# golgi_bot_H_bridge.net
KiCad netlist of a schematic drawn in Altium Designer
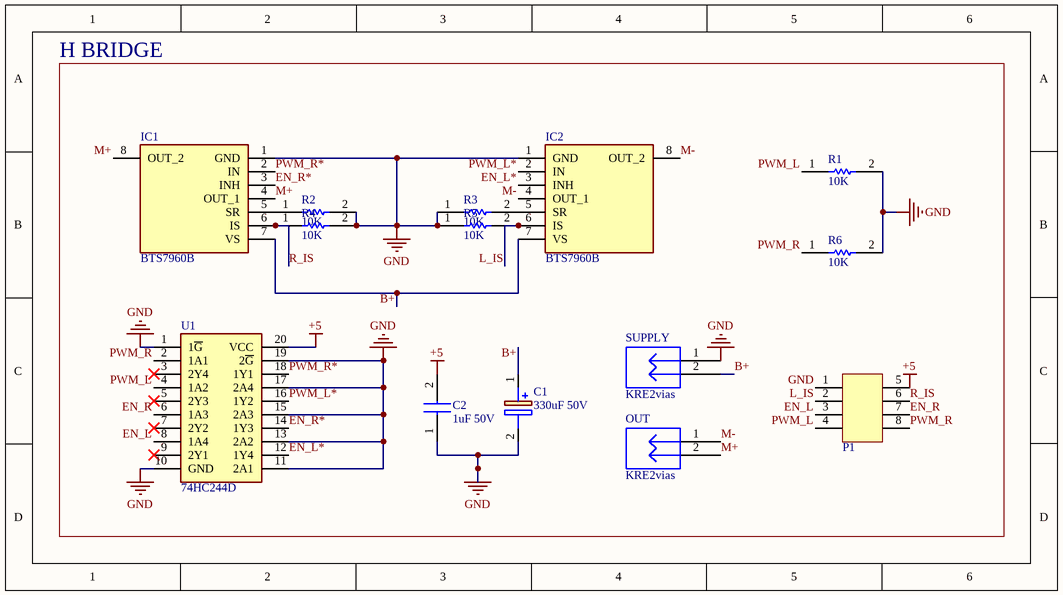
[diagram p0: golgi_bot_H_bridge.SchDoc]

(export (version "E")
  (design (tool "Eeschema 10.0.6"))
  (components
    (comp (ref "C1")
      (value "330uF 50V")
      (footprint "golgi_bot_H_bridge:CAPPRD750W85D1600H1650")
      (description "capacitor 330uf 50V")
      (fields (field (name "MANUFACTURER_PART_NUMBER") "EEU-TA1H331S"))
      (libsource (lib "golgi_bot_H_bridge") (part "Capacitor eletrolítico"))
    )
    (comp (ref "C2")
      (value "1uF 50V")
      (footprint "SamacSys:CAPC3216X180N")
      (description "Capacitor")
      (fields
        (field (name "MANUFACTURER_PART_NUMBER") "C3216X5R0J226M160AA")
        (field (name "MOUSER PART NUMBER") "810-C3216X5R0J226M-6")
      )
      (libsource (lib "golgi_bot_H_bridge") (part "Capacitor Cerâmico 1206"))
    )
    (comp (ref "IC1")
      (value "BTS7960B")
      (footprint "BTS7960B")
      (description "Integrated Circuit")
      (libsource (lib "") (part "BTS7960B_1"))
    )
    (comp (ref "IC2")
      (value "BTS7960B")
      (footprint "BTS7960B")
      (description "Integrated Circuit")
      (libsource (lib "golgi_bot_H_bridge") (part "BTS7960B"))
    )
    (comp (ref "OUT")
      (value "KRE2vias")
      (footprint "KRE2-2vias")
      (description "Conector 2 vias")
      (libsource (lib "golgi_bot_H_bridge") (part "KRE2vias"))
    )
    (comp (ref "P1")
      (value "PIN BAR 2X4")
      (footprint "MALE PIN BAR 2X4")
      (fields (field (name "MANUFACTURER") "Cromax"))
      (libsource (lib "golgi_bot_H_bridge") (part "Male pin bar 2x4"))
    )
    (comp (ref "R1")
      (value "10K")
      (footprint "RESC3216X60N")
      (fields
        (field (name "MANUFACTURER_PART_NUMBER") "CRCW12064K70FKEA")
        (field (name "MOUSER PART NUMBER") "71-CRCW1206-4.7K-E3")
      )
      (libsource (lib "golgi_bot_H_bridge") (part "Resistor 1206"))
    )
    (comp (ref "R2")
      (value "10K")
      (footprint "RESC3216X60N")
      (fields
        (field (name "MANUFACTURER_PART_NUMBER") "CRCW12064K70FKEA")
        (field (name "MOUSER PART NUMBER") "71-CRCW1206-4.7K-E3")
      )
      (libsource (lib "golgi_bot_H_bridge") (part "Resistor 1206"))
    )
    (comp (ref "R3")
      (value "10K")
      (footprint "RESC3216X60N")
      (fields
        (field (name "MANUFACTURER_PART_NUMBER") "CRCW12064K70FKEA")
        (field (name "MOUSER PART NUMBER") "71-CRCW1206-4.7K-E3")
      )
      (libsource (lib "golgi_bot_H_bridge") (part "Resistor 1206"))
    )
    (comp (ref "R4")
      (value "10K")
      (footprint "RESC3216X60N")
      (fields
        (field (name "MANUFACTURER_PART_NUMBER") "CRCW12064K70FKEA")
        (field (name "MOUSER PART NUMBER") "71-CRCW1206-4.7K-E3")
      )
      (libsource (lib "golgi_bot_H_bridge") (part "Resistor 1206"))
    )
    (comp (ref "R5")
      (value "10K")
      (footprint "RESC3216X60N")
      (fields
        (field (name "MANUFACTURER_PART_NUMBER") "CRCW12064K70FKEA")
        (field (name "MOUSER PART NUMBER") "71-CRCW1206-4.7K-E3")
      )
      (libsource (lib "golgi_bot_H_bridge") (part "Resistor 1206"))
    )
    (comp (ref "R6")
      (value "10K")
      (footprint "RESC3216X60N")
      (fields
        (field (name "MANUFACTURER_PART_NUMBER") "CRCW12064K70FKEA")
        (field (name "MOUSER PART NUMBER") "71-CRCW1206-4.7K-E3")
      )
      (libsource (lib "golgi_bot_H_bridge") (part "Resistor 1206"))
    )
    (comp (ref "SUPPLY")
      (value "KRE2vias")
      (footprint "KRE2-2vias")
      (description "Conector 2 vias")
      (libsource (lib "golgi_bot_H_bridge") (part "KRE2vias"))
    )
    (comp (ref "U1")
      (value "74HC244D")
      (footprint "SOIC127P1030X250-20N")
      (description "Integrated Circuit")
      (fields (field (name "MOUSER PART NUMBER") "757-74HC244D"))
      (libsource (lib "golgi_bot_H_bridge") (part "74HC244D"))
    )
  )
  (nets
    (net (code "1") (name "+5") (class "Default")
      (node (ref "C2") (pin "2") (pinfunction "2_2") (pintype "passive"))
      (node (ref "P1") (pin "5") (pintype "passive"))
      (node (ref "U1") (pin "20") (pinfunction "VCC_20") (pintype "passive"))
    )
    (net (code "2") (name "/B+") (class "Default")
      (node (ref "C1") (pin "1") (pinfunction "+_1") (pintype "passive"))
      (node (ref "IC1") (pin "7") (pinfunction "VS_7") (pintype "passive"))
      (node (ref "IC2") (pin "7") (pinfunction "VS_7") (pintype "passive"))
      (node (ref "SUPPLY") (pin "2") (pintype "passive"))
    )
    (net (code "3") (name "/EN_L") (class "Default")
      (node (ref "P1") (pin "3") (pintype "passive"))
      (node (ref "U1") (pin "8") (pinfunction "1A4_8") (pintype "passive"))
    )
    (net (code "4") (name "/EN_L*") (class "Default")
      (node (ref "IC2") (pin "3") (pinfunction "INH_3") (pintype "passive"))
      (node (ref "U1") (pin "12") (pinfunction "1Y4_12") (pintype "passive"))
    )
    (net (code "5") (name "/EN_R") (class "Default")
      (node (ref "P1") (pin "7") (pintype "passive"))
      (node (ref "U1") (pin "6") (pinfunction "1A3_6") (pintype "passive"))
    )
    (net (code "6") (name "/EN_R*") (class "Default")
      (node (ref "IC1") (pin "3") (pinfunction "INH_3") (pintype "passive"))
      (node (ref "U1") (pin "14") (pinfunction "1Y3_14") (pintype "passive"))
    )
    (net (code "7") (name "/L_IS") (class "Default")
      (node (ref "IC2") (pin "6") (pinfunction "IS_6") (pintype "passive"))
      (node (ref "P1") (pin "2") (pintype "passive"))
      (node (ref "R5") (pin "2") (pinfunction "2_2") (pintype "passive"))
    )
    (net (code "8") (name "/M+") (class "Default")
      (node (ref "IC1") (pin "4") (pinfunction "OUT_1_4") (pintype "passive"))
      (node (ref "IC1") (pin "8") (pinfunction "OUT_2_8") (pintype "passive"))
      (node (ref "OUT") (pin "2") (pintype "passive"))
    )
    (net (code "9") (name "/M-") (class "Default")
      (node (ref "IC2") (pin "4") (pinfunction "OUT_1_4") (pintype "passive"))
      (node (ref "IC2") (pin "8") (pinfunction "OUT_2_8") (pintype "passive"))
      (node (ref "OUT") (pin "1") (pintype "passive"))
    )
    (net (code "10") (name "/PWM_L") (class "Default")
      (node (ref "P1") (pin "4") (pintype "passive"))
      (node (ref "R1") (pin "1") (pinfunction "1_1") (pintype "passive"))
      (node (ref "U1") (pin "4") (pinfunction "1A2_4") (pintype "passive"))
    )
    (net (code "11") (name "/PWM_L*") (class "Default")
      (node (ref "IC2") (pin "2") (pinfunction "IN_2") (pintype "passive"))
      (node (ref "U1") (pin "16") (pinfunction "1Y2_16") (pintype "passive"))
    )
    (net (code "12") (name "/PWM_R") (class "Default")
      (node (ref "P1") (pin "8") (pintype "passive"))
      (node (ref "R6") (pin "1") (pinfunction "1_1") (pintype "passive"))
      (node (ref "U1") (pin "2") (pinfunction "1A1_2") (pintype "passive"))
    )
    (net (code "13") (name "/PWM_R*") (class "Default")
      (node (ref "IC1") (pin "2") (pinfunction "IN_2") (pintype "passive"))
      (node (ref "U1") (pin "18") (pinfunction "1Y1_18") (pintype "passive"))
    )
    (net (code "14") (name "/R_IS") (class "Default")
      (node (ref "IC1") (pin "6") (pinfunction "IS_6") (pintype "passive"))
      (node (ref "P1") (pin "6") (pintype "passive"))
      (node (ref "R4") (pin "1") (pinfunction "1_1") (pintype "passive"))
    )
    (net (code "15") (name "GND") (class "Default")
      (node (ref "C1") (pin "2") (pinfunction "-_2") (pintype "passive"))
      (node (ref "C2") (pin "1") (pinfunction "1_1") (pintype "passive"))
      (node (ref "IC1") (pin "1") (pinfunction "GND_1") (pintype "passive"))
      (node (ref "IC2") (pin "1") (pinfunction "GND_1") (pintype "passive"))
      (node (ref "P1") (pin "1") (pintype "passive"))
      (node (ref "R1") (pin "2") (pinfunction "2_2") (pintype "passive"))
      (node (ref "R2") (pin "2") (pinfunction "2_2") (pintype "passive"))
      (node (ref "R3") (pin "1") (pinfunction "1_1") (pintype "passive"))
      (node (ref "R4") (pin "2") (pinfunction "2_2") (pintype "passive"))
      (node (ref "R5") (pin "1") (pinfunction "1_1") (pintype "passive"))
      (node (ref "R6") (pin "2") (pinfunction "2_2") (pintype "passive"))
      (node (ref "SUPPLY") (pin "1") (pintype "passive"))
      (node (ref "U1") (pin "1") (pinfunction "1~{G}_1") (pintype "passive"))
      (node (ref "U1") (pin "10") (pinfunction "GND_10") (pintype "passive"))
      (node (ref "U1") (pin "11") (pinfunction "2A1_11") (pintype "passive"))
      (node (ref "U1") (pin "13") (pinfunction "2A2_13") (pintype "passive"))
      (node (ref "U1") (pin "15") (pinfunction "2A3_15") (pintype "passive"))
      (node (ref "U1") (pin "17") (pinfunction "2A4_17") (pintype "passive"))
      (node (ref "U1") (pin "19") (pinfunction "2~{G}_19") (pintype "passive"))
    )
    (net (code "16") (name "Net-(IC1-SR)") (class "Default")
      (node (ref "IC1") (pin "5") (pinfunction "SR_5") (pintype "passive"))
      (node (ref "R2") (pin "1") (pinfunction "1_1") (pintype "passive"))
    )
    (net (code "17") (name "Net-(IC2-SR)") (class "Default")
      (node (ref "IC2") (pin "5") (pinfunction "SR_5") (pintype "passive"))
      (node (ref "R3") (pin "2") (pinfunction "2_2") (pintype "passive"))
    )
    (net (code "18") (name "unconnected-(U1-2Y1-Pad9)") (class "Default")
      (node (ref "U1") (pin "9") (pinfunction "2Y1_9") (pintype "passive+no_connect"))
    )
    (net (code "19") (name "unconnected-(U1-2Y2-Pad7)") (class "Default")
      (node (ref "U1") (pin "7") (pinfunction "2Y2_7") (pintype "passive+no_connect"))
    )
    (net (code "20") (name "unconnected-(U1-2Y3-Pad5)") (class "Default")
      (node (ref "U1") (pin "5") (pinfunction "2Y3_5") (pintype "passive+no_connect"))
    )
    (net (code "21") (name "unconnected-(U1-2Y4-Pad3)") (class "Default")
      (node (ref "U1") (pin "3") (pinfunction "2Y4_3") (pintype "passive+no_connect"))
    )
  )
)
